# NEAR_DAUGHTER.net
KiCad netlist of a schematic drawn in Altium Designer
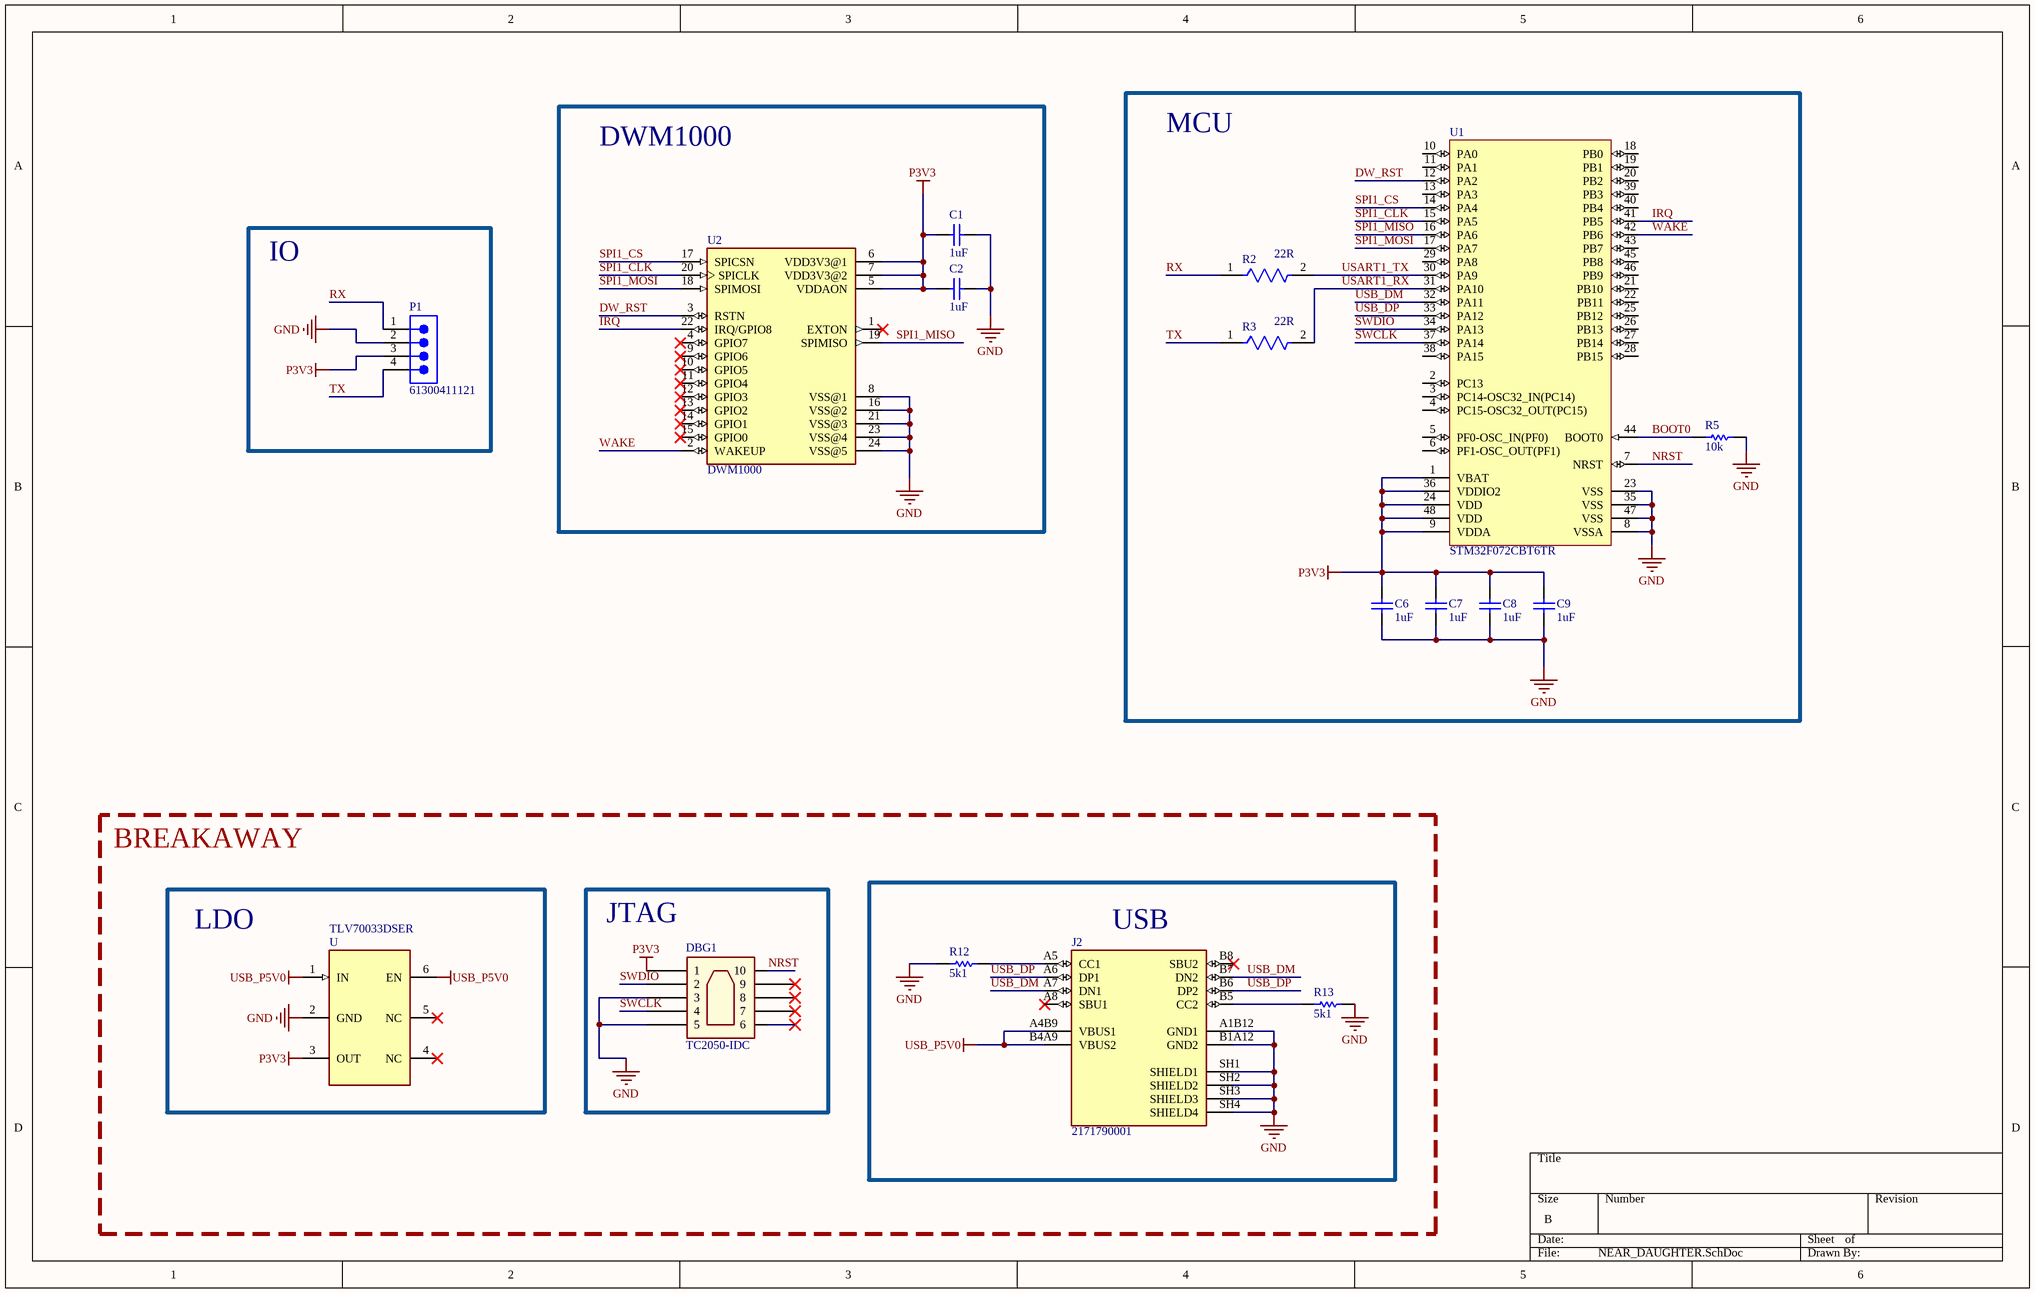
[diagram p0: NEAR_DAUGHTER.SchDoc]

(export (version "E")
  (design (tool "Eeschema 10.0.6"))
  (components
    (comp (ref "C1")
      (value "1uF")
      (footprint "CAP_0603")
      (description "Cap Ceramic 1uF 25V X7R 10% Pad SMD 0603 125C Automotive T/R")
      (fields (field (name "TOLERANCE") "10%"))
      (libsource (lib "MRacing FSAE") (part "CAP"))
    )
    (comp (ref "C2")
      (value "1uF")
      (footprint "CAP_0603")
      (description "Cap Ceramic 1uF 25V X7R 10% Pad SMD 0603 125C Automotive T/R")
      (fields (field (name "TOLERANCE") "10%"))
      (libsource (lib "MRacing FSAE") (part "CAP"))
    )
    (comp (ref "C6")
      (value "1uF")
      (footprint "CAP_0603")
      (description "Cap Ceramic 1uF 25V X7R 10% Pad SMD 0603 125C Automotive T/R")
      (fields (field (name "TOLERANCE") "10%"))
      (libsource (lib "MRacing FSAE") (part "CAP"))
    )
    (comp (ref "C7")
      (value "1uF")
      (footprint "CAP_0603")
      (description "Cap Ceramic 1uF 25V X7R 10% Pad SMD 0603 125C Automotive T/R")
      (fields (field (name "TOLERANCE") "10%"))
      (libsource (lib "MRacing FSAE") (part "CAP"))
    )
    (comp (ref "C8")
      (value "1uF")
      (footprint "CAP_0603")
      (description "Cap Ceramic 1uF 25V X7R 10% Pad SMD 0603 125C Automotive T/R")
      (fields (field (name "TOLERANCE") "10%"))
      (libsource (lib "MRacing FSAE") (part "CAP"))
    )
    (comp (ref "C9")
      (value "1uF")
      (footprint "CAP_0603")
      (description "Cap Ceramic 1uF 25V X7R 10% Pad SMD 0603 125C Automotive T/R")
      (fields (field (name "TOLERANCE") "10%"))
      (libsource (lib "MRacing FSAE") (part "CAP"))
    )
    (comp (ref "DBG1")
      (value "TC2050-IDC")
      (footprint "TC2050-IDC-Footprint-2")
      (description "CBL PLUG-OF-NAILS 10-PIN W/LEGS")
      (libsource (lib "MRacing FSAE") (part "TC2050-IDC-Symbol-1"))
    )
    (comp (ref "J2")
      (value "2171790001")
      (footprint "MOLEX_2171790001")
      (description "USB Type C - Connector, Top-mount SMT, 16pos")
      (fields (field (name "MP") "217179-0001") (field (name "MF") "Molex"))
      (libsource (lib "MRacing FSAE") (part "2171790001"))
    )
    (comp (ref "P1")
      (value "61300411121")
      (footprint "61300411121")
      (description "WR-PHD Pin Header, THT, Vertical, pitch 2.54mm, 1 Row, 4P")
      (fields (field (name "MANUFACTURER") "Wurth Elektronik"))
      (libsource (lib "MRacing FSAE") (part "62000411121"))
    )
    (comp (ref "R2")
      (value "22R")
      (footprint "FP-CPF0603-MFG")
      (description "RES SMD 22Ω 0.1% 1/16W 0603")
      (fields
        (field (name "MANUFACTURER") "TE Connectivity")
        (field (name "OCTOPART") "https://octopart.com/cpf0603b22re1-te+connectivity-9539398")
      )
      (libsource (lib "Altium Content Vault") (part "1029c3af85768c4190bb7ad29bc67b5"))
    )
    (comp (ref "R3")
      (value "22R")
      (footprint "FP-CPF0603-MFG")
      (description "RES SMD 22Ω 0.1% 1/16W 0603")
      (fields
        (field (name "MANUFACTURER") "TE Connectivity")
        (field (name "OCTOPART") "https://octopart.com/cpf0603b22re1-te+connectivity-9539398")
      )
      (libsource (lib "Altium Content Vault") (part "1029c3af85768c4190bb7ad29bc67b5"))
    )
    (comp (ref "R5")
      (value "10k")
      (footprint "RESC1609X55X30LL15T15")
      (description "Chip Resistor, 10 KOhm, +/- 1%, 0.1 W, -55 to 155 degC, 0603 (1608 Metric), RoHS, Tape and Reel")
      (fields (field (name "TOLERANCE") "1%") (field (name "MANUFACTURER") "Panasonic"))
      (libsource (lib "Altium Content Vault") (part "RES-2"))
    )
    (comp (ref "R12")
      (value "5k1")
      (footprint "RESC1608X55X25ML10T15")
      (fields (field (name "MANUFACTURER") "Yageo") (field (name "PART NUMBER") "RC0603FR-075K1L"))
      (libsource (lib "Altium Content Vault") (part "RES"))
    )
    (comp (ref "R13")
      (value "5k1")
      (footprint "RESC1608X55X25ML10T15")
      (fields (field (name "MANUFACTURER") "Yageo") (field (name "PART NUMBER") "RC0603FR-075K1L"))
      (libsource (lib "Altium Content Vault") (part "RES"))
    )
    (comp (ref "U")
      (value "TLV70033DSER")
      (footprint "SON50P150X150X80-6N")
      (description "Linear Voltage Regulator IC 1 Output 200mA 6-WSON _1.5x1.5_")
      (fields (field (name "MF") "Texas Instruments"))
      (libsource (lib "MRacing FSAE") (part "TLV70033DSER"))
    )
    (comp (ref "U1")
      (value "STM32F072CBT6TR")
      (footprint "STM-LQFP48_M")
      (libsource (lib "Altium Content Vault") (part "MC-ARM-STM32F07X-LQFP48"))
    )
    (comp (ref "U2")
      (value "DWM1000")
      (footprint "XCVR_DWM1000")
      (description "802.15.4 IR-UWB Transceiver Module 3.5GHz ~ 6.5GHz Integrated, Chip Surface Mount")
      (fields (field (name "MF") "Decawave Limited"))
      (libsource (lib "MRacing FSAE") (part "DWM1000"))
    )
  )
  (nets
    (net (code "1") (name "/BOOT0") (class "Default")
      (node (ref "R5") (pin "2") (pinfunction "2_2") (pintype "passive"))
      (node (ref "U1") (pin "44") (pinfunction "BOOT0_44") (pintype "input"))
    )
    (net (code "2") (name "/DW_RST") (class "Default")
      (node (ref "U1") (pin "12") (pinfunction "PA2_12") (pintype "bidirectional"))
      (node (ref "U2") (pin "3") (pinfunction "RSTN_3") (pintype "bidirectional"))
    )
    (net (code "3") (name "/IRQ") (class "Default")
      (node (ref "U1") (pin "41") (pinfunction "PB5_41") (pintype "bidirectional"))
      (node (ref "U2") (pin "22") (pinfunction "IRQ/GPIO8_22") (pintype "bidirectional"))
    )
    (net (code "4") (name "/NRST") (class "Default")
      (node (ref "DBG1") (pin "10") (pinfunction "10_10") (pintype "passive"))
      (node (ref "U1") (pin "7") (pinfunction "NRST_7") (pintype "bidirectional"))
    )
    (net (code "5") (name "/RX") (class "Default")
      (node (ref "P1") (pin "1") (pinfunction "1_1") (pintype "passive"))
      (node (ref "R2") (pin "1") (pinfunction "1_1") (pintype "passive"))
    )
    (net (code "6") (name "/SPI1_CLK") (class "Default")
      (node (ref "U1") (pin "15") (pinfunction "PA5_15") (pintype "bidirectional"))
      (node (ref "U2") (pin "20") (pinfunction "SPICLK_20") (pintype "input"))
    )
    (net (code "7") (name "/SPI1_CS") (class "Default")
      (node (ref "U1") (pin "14") (pinfunction "PA4_14") (pintype "bidirectional"))
      (node (ref "U2") (pin "17") (pinfunction "SPICSN_17") (pintype "input"))
    )
    (net (code "8") (name "/SPI1_MISO") (class "Default")
      (node (ref "U1") (pin "16") (pinfunction "PA6_16") (pintype "bidirectional"))
      (node (ref "U2") (pin "19") (pinfunction "SPIMISO_19") (pintype "output"))
    )
    (net (code "9") (name "/SPI1_MOSI") (class "Default")
      (node (ref "U1") (pin "17") (pinfunction "PA7_17") (pintype "bidirectional"))
      (node (ref "U2") (pin "18") (pinfunction "SPIMOSI_18") (pintype "input"))
    )
    (net (code "10") (name "/SWCLK") (class "Default")
      (node (ref "DBG1") (pin "4") (pinfunction "4_4") (pintype "passive"))
      (node (ref "U1") (pin "37") (pinfunction "PA14_37") (pintype "bidirectional"))
    )
    (net (code "11") (name "/SWDIO") (class "Default")
      (node (ref "DBG1") (pin "2") (pinfunction "2_2") (pintype "passive"))
      (node (ref "U1") (pin "34") (pinfunction "PA13_34") (pintype "bidirectional"))
    )
    (net (code "12") (name "/TX") (class "Default")
      (node (ref "P1") (pin "4") (pinfunction "4_4") (pintype "passive"))
      (node (ref "R3") (pin "1") (pinfunction "1_1") (pintype "passive"))
    )
    (net (code "13") (name "/USART1_RX") (class "Default")
      (node (ref "R3") (pin "2") (pinfunction "2_2") (pintype "passive"))
      (node (ref "U1") (pin "31") (pinfunction "PA10_31") (pintype "bidirectional"))
    )
    (net (code "14") (name "/USART1_TX") (class "Default")
      (node (ref "R2") (pin "2") (pinfunction "2_2") (pintype "passive"))
      (node (ref "U1") (pin "30") (pinfunction "PA9_30") (pintype "bidirectional"))
    )
    (net (code "15") (name "/USB_DM") (class "Default")
      (node (ref "J2") (pin "A7") (pinfunction "DN1_A7") (pintype "bidirectional"))
      (node (ref "J2") (pin "B7") (pinfunction "DN2_B7") (pintype "bidirectional"))
      (node (ref "U1") (pin "32") (pinfunction "PA11_32") (pintype "bidirectional"))
    )
    (net (code "16") (name "/USB_DP") (class "Default")
      (node (ref "J2") (pin "A6") (pinfunction "DP1_A6") (pintype "bidirectional"))
      (node (ref "J2") (pin "B6") (pinfunction "DP2_B6") (pintype "bidirectional"))
      (node (ref "U1") (pin "33") (pinfunction "PA12_33") (pintype "bidirectional"))
    )
    (net (code "17") (name "/WAKE") (class "Default")
      (node (ref "U1") (pin "42") (pinfunction "PB6_42") (pintype "bidirectional"))
      (node (ref "U2") (pin "2") (pinfunction "WAKEUP_2") (pintype "bidirectional"))
    )
    (net (code "18") (name "GND") (class "Default")
      (node (ref "C1") (pin "2") (pinfunction "2_2") (pintype "passive"))
      (node (ref "C2") (pin "2") (pinfunction "2_2") (pintype "passive"))
      (node (ref "C6") (pin "1") (pinfunction "1_1") (pintype "passive"))
      (node (ref "C7") (pin "1") (pinfunction "1_1") (pintype "passive"))
      (node (ref "C8") (pin "1") (pinfunction "1_1") (pintype "passive"))
      (node (ref "C9") (pin "1") (pinfunction "1_1") (pintype "passive"))
      (node (ref "DBG1") (pin "3") (pinfunction "3_3") (pintype "passive"))
      (node (ref "DBG1") (pin "5") (pinfunction "5_5") (pintype "passive"))
      (node (ref "J2") (pin "A1B12") (pinfunction "GND1_A1B12") (pintype "power_in"))
      (node (ref "J2") (pin "B1A12") (pinfunction "GND2_B1A12") (pintype "power_in"))
      (node (ref "J2") (pin "SH1") (pinfunction "SHIELD1_SH1") (pintype "passive"))
      (node (ref "J2") (pin "SH2") (pinfunction "SHIELD2_SH2") (pintype "passive"))
      (node (ref "J2") (pin "SH3") (pinfunction "SHIELD3_SH3") (pintype "passive"))
      (node (ref "J2") (pin "SH4") (pinfunction "SHIELD4_SH4") (pintype "passive"))
      (node (ref "P1") (pin "2") (pinfunction "2_2") (pintype "passive"))
      (node (ref "R12") (pin "2") (pinfunction "2_2") (pintype "passive"))
      (node (ref "R13") (pin "1") (pinfunction "1_1") (pintype "passive"))
      (node (ref "R5") (pin "1") (pinfunction "1_1") (pintype "passive"))
      (node (ref "U") (pin "2") (pinfunction "GND_2") (pintype "power_in"))
      (node (ref "U1") (pin "23") (pinfunction "VSS_23") (pintype "power_in"))
      (node (ref "U1") (pin "35") (pinfunction "VSS_35") (pintype "power_in"))
      (node (ref "U1") (pin "47") (pinfunction "VSS_47") (pintype "power_in"))
      (node (ref "U1") (pin "8") (pinfunction "VSSA_8") (pintype "power_in"))
      (node (ref "U2") (pin "16") (pinfunction "VSS@2_16") (pintype "power_in"))
      (node (ref "U2") (pin "21") (pinfunction "VSS@3_21") (pintype "power_in"))
      (node (ref "U2") (pin "23") (pinfunction "VSS@4_23") (pintype "power_in"))
      (node (ref "U2") (pin "24") (pinfunction "VSS@5_24") (pintype "power_in"))
      (node (ref "U2") (pin "8") (pinfunction "VSS@1_8") (pintype "power_in"))
    )
    (net (code "19") (name "Net-(J2-CC1)") (class "Default")
      (node (ref "J2") (pin "A5") (pinfunction "CC1_A5") (pintype "bidirectional"))
      (node (ref "R12") (pin "1") (pinfunction "1_1") (pintype "passive"))
    )
    (net (code "20") (name "Net-(J2-CC2)") (class "Default")
      (node (ref "J2") (pin "B5") (pinfunction "CC2_B5") (pintype "bidirectional"))
      (node (ref "R13") (pin "2") (pinfunction "2_2") (pintype "passive"))
    )
    (net (code "21") (name "P3V3") (class "Default")
      (node (ref "C1") (pin "1") (pinfunction "1_1") (pintype "passive"))
      (node (ref "C2") (pin "1") (pinfunction "1_1") (pintype "passive"))
      (node (ref "C6") (pin "2") (pinfunction "2_2") (pintype "passive"))
      (node (ref "C7") (pin "2") (pinfunction "2_2") (pintype "passive"))
      (node (ref "C8") (pin "2") (pinfunction "2_2") (pintype "passive"))
      (node (ref "C9") (pin "2") (pinfunction "2_2") (pintype "passive"))
      (node (ref "DBG1") (pin "1") (pinfunction "1_1") (pintype "passive"))
      (node (ref "P1") (pin "3") (pinfunction "3_3") (pintype "passive"))
      (node (ref "U") (pin "3") (pinfunction "OUT_3") (pintype "power_in"))
      (node (ref "U1") (pin "1") (pinfunction "VBAT_1") (pintype "power_in"))
      (node (ref "U1") (pin "24") (pinfunction "VDD_24") (pintype "power_in"))
      (node (ref "U1") (pin "36") (pinfunction "VDDIO2_36") (pintype "power_in"))
      (node (ref "U1") (pin "48") (pinfunction "VDD_48") (pintype "power_in"))
      (node (ref "U1") (pin "9") (pinfunction "VDDA_9") (pintype "power_in"))
      (node (ref "U2") (pin "5") (pinfunction "VDDAON_5") (pintype "power_in"))
      (node (ref "U2") (pin "6") (pinfunction "VDD3V3@1_6") (pintype "power_in"))
      (node (ref "U2") (pin "7") (pinfunction "VDD3V3@2_7") (pintype "power_in"))
    )
    (net (code "22") (name "USB_P5V0") (class "Default")
      (node (ref "J2") (pin "A4B9") (pinfunction "VBUS1_A4B9") (pintype "power_in"))
      (node (ref "J2") (pin "B4A9") (pinfunction "VBUS2_B4A9") (pintype "power_in"))
      (node (ref "U") (pin "1") (pinfunction "IN_1") (pintype "input"))
      (node (ref "U") (pin "6") (pinfunction "EN_6") (pintype "power_in"))
    )
    (net (code "23") (name "unconnected-(DBG1-Pad6)") (class "Default")
      (node (ref "DBG1") (pin "6") (pinfunction "6_6") (pintype "passive+no_connect"))
    )
    (net (code "24") (name "unconnected-(DBG1-Pad7)") (class "Default")
      (node (ref "DBG1") (pin "7") (pinfunction "7_7") (pintype "passive+no_connect"))
    )
    (net (code "25") (name "unconnected-(DBG1-Pad8)") (class "Default")
      (node (ref "DBG1") (pin "8") (pinfunction "8_8") (pintype "passive+no_connect"))
    )
    (net (code "26") (name "unconnected-(DBG1-Pad9)") (class "Default")
      (node (ref "DBG1") (pin "9") (pinfunction "9_9") (pintype "passive+no_connect"))
    )
    (net (code "27") (name "unconnected-(J2-SBU1-PadA8)") (class "Default")
      (node (ref "J2") (pin "A8") (pinfunction "SBU1_A8") (pintype "bidirectional+no_connect"))
    )
    (net (code "28") (name "unconnected-(J2-SBU2-PadB8)") (class "Default")
      (node (ref "J2") (pin "B8") (pinfunction "SBU2_B8") (pintype "bidirectional+no_connect"))
    )
    (net (code "29") (name "unconnected-(U-NC-Pad4)") (class "Default")
      (node (ref "U") (pin "4") (pinfunction "NC_4") (pintype "power_in+no_connect"))
    )
    (net (code "30") (name "unconnected-(U-NC-Pad5)") (class "Default")
      (node (ref "U") (pin "5") (pinfunction "NC_5") (pintype "power_in+no_connect"))
    )
    (net (code "31") (name "unconnected-(U1-PA0-Pad10)") (class "Default")
      (node (ref "U1") (pin "10") (pinfunction "PA0_10") (pintype "bidirectional"))
    )
    (net (code "32") (name "unconnected-(U1-PA1-Pad11)") (class "Default")
      (node (ref "U1") (pin "11") (pinfunction "PA1_11") (pintype "bidirectional"))
    )
    (net (code "33") (name "unconnected-(U1-PA3-Pad13)") (class "Default")
      (node (ref "U1") (pin "13") (pinfunction "PA3_13") (pintype "bidirectional"))
    )
    (net (code "34") (name "unconnected-(U1-PA8-Pad29)") (class "Default")
      (node (ref "U1") (pin "29") (pinfunction "PA8_29") (pintype "bidirectional"))
    )
    (net (code "35") (name "unconnected-(U1-PA15-Pad38)") (class "Default")
      (node (ref "U1") (pin "38") (pinfunction "PA15_38") (pintype "bidirectional"))
    )
    (net (code "36") (name "unconnected-(U1-PB0-Pad18)") (class "Default")
      (node (ref "U1") (pin "18") (pinfunction "PB0_18") (pintype "bidirectional"))
    )
    (net (code "37") (name "unconnected-(U1-PB1-Pad19)") (class "Default")
      (node (ref "U1") (pin "19") (pinfunction "PB1_19") (pintype "bidirectional"))
    )
    (net (code "38") (name "unconnected-(U1-PB2-Pad20)") (class "Default")
      (node (ref "U1") (pin "20") (pinfunction "PB2_20") (pintype "bidirectional"))
    )
    (net (code "39") (name "unconnected-(U1-PB3-Pad39)") (class "Default")
      (node (ref "U1") (pin "39") (pinfunction "PB3_39") (pintype "bidirectional"))
    )
    (net (code "40") (name "unconnected-(U1-PB4-Pad40)") (class "Default")
      (node (ref "U1") (pin "40") (pinfunction "PB4_40") (pintype "bidirectional"))
    )
    (net (code "41") (name "unconnected-(U1-PB7-Pad43)") (class "Default")
      (node (ref "U1") (pin "43") (pinfunction "PB7_43") (pintype "bidirectional"))
    )
    (net (code "42") (name "unconnected-(U1-PB8-Pad45)") (class "Default")
      (node (ref "U1") (pin "45") (pinfunction "PB8_45") (pintype "bidirectional"))
    )
    (net (code "43") (name "unconnected-(U1-PB9-Pad46)") (class "Default")
      (node (ref "U1") (pin "46") (pinfunction "PB9_46") (pintype "bidirectional"))
    )
    (net (code "44") (name "unconnected-(U1-PB10-Pad21)") (class "Default")
      (node (ref "U1") (pin "21") (pinfunction "PB10_21") (pintype "bidirectional"))
    )
    (net (code "45") (name "unconnected-(U1-PB11-Pad22)") (class "Default")
      (node (ref "U1") (pin "22") (pinfunction "PB11_22") (pintype "bidirectional"))
    )
    (net (code "46") (name "unconnected-(U1-PB12-Pad25)") (class "Default")
      (node (ref "U1") (pin "25") (pinfunction "PB12_25") (pintype "bidirectional"))
    )
    (net (code "47") (name "unconnected-(U1-PB13-Pad26)") (class "Default")
      (node (ref "U1") (pin "26") (pinfunction "PB13_26") (pintype "bidirectional"))
    )
    (net (code "48") (name "unconnected-(U1-PB14-Pad27)") (class "Default")
      (node (ref "U1") (pin "27") (pinfunction "PB14_27") (pintype "bidirectional"))
    )
    (net (code "49") (name "unconnected-(U1-PB15-Pad28)") (class "Default")
      (node (ref "U1") (pin "28") (pinfunction "PB15_28") (pintype "bidirectional"))
    )
    (net (code "50") (name "unconnected-(U1-PC13-Pad2)") (class "Default")
      (node (ref "U1") (pin "2") (pinfunction "PC13_2") (pintype "bidirectional"))
    )
    (net (code "51") (name "unconnected-(U1-PC14-OSC32_IN(PC14)-Pad3)") (class "Default")
      (node (ref "U1") (pin "3") (pinfunction "PC14-OSC32_IN(PC14)_3") (pintype "bidirectional"))
    )
    (net (code "52") (name "unconnected-(U1-PC15-OSC32_OUT(PC15)-Pad4)") (class "Default")
      (node (ref "U1") (pin "4") (pinfunction "PC15-OSC32_OUT(PC15)_4") (pintype "bidirectional"))
    )
    (net (code "53") (name "unconnected-(U1-PF0-OSC_IN(PF0)-Pad5)") (class "Default")
      (node (ref "U1") (pin "5") (pinfunction "PF0-OSC_IN(PF0)_5") (pintype "bidirectional"))
    )
    (net (code "54") (name "unconnected-(U1-PF1-OSC_OUT(PF1)-Pad6)") (class "Default")
      (node (ref "U1") (pin "6") (pinfunction "PF1-OSC_OUT(PF1)_6") (pintype "bidirectional"))
    )
    (net (code "55") (name "unconnected-(U2-EXTON-Pad1)") (class "Default")
      (node (ref "U2") (pin "1") (pinfunction "EXTON_1") (pintype "output+no_connect"))
    )
    (net (code "56") (name "unconnected-(U2-GPIO0-Pad15)") (class "Default")
      (node (ref "U2") (pin "15") (pinfunction "GPIO0_15") (pintype "bidirectional+no_connect"))
    )
    (net (code "57") (name "unconnected-(U2-GPIO1-Pad14)") (class "Default")
      (node (ref "U2") (pin "14") (pinfunction "GPIO1_14") (pintype "bidirectional+no_connect"))
    )
    (net (code "58") (name "unconnected-(U2-GPIO2-Pad13)") (class "Default")
      (node (ref "U2") (pin "13") (pinfunction "GPIO2_13") (pintype "bidirectional+no_connect"))
    )
    (net (code "59") (name "unconnected-(U2-GPIO3-Pad12)") (class "Default")
      (node (ref "U2") (pin "12") (pinfunction "GPIO3_12") (pintype "bidirectional+no_connect"))
    )
    (net (code "60") (name "unconnected-(U2-GPIO4-Pad11)") (class "Default")
      (node (ref "U2") (pin "11") (pinfunction "GPIO4_11") (pintype "bidirectional+no_connect"))
    )
    (net (code "61") (name "unconnected-(U2-GPIO5-Pad10)") (class "Default")
      (node (ref "U2") (pin "10") (pinfunction "GPIO5_10") (pintype "bidirectional+no_connect"))
    )
    (net (code "62") (name "unconnected-(U2-GPIO6-Pad9)") (class "Default")
      (node (ref "U2") (pin "9") (pinfunction "GPIO6_9") (pintype "bidirectional+no_connect"))
    )
    (net (code "63") (name "unconnected-(U2-GPIO7-Pad4)") (class "Default")
      (node (ref "U2") (pin "4") (pinfunction "GPIO7_4") (pintype "bidirectional+no_connect"))
    )
  )
)
